# alarm.net
KiCad netlist of a schematic drawn in EAGLE
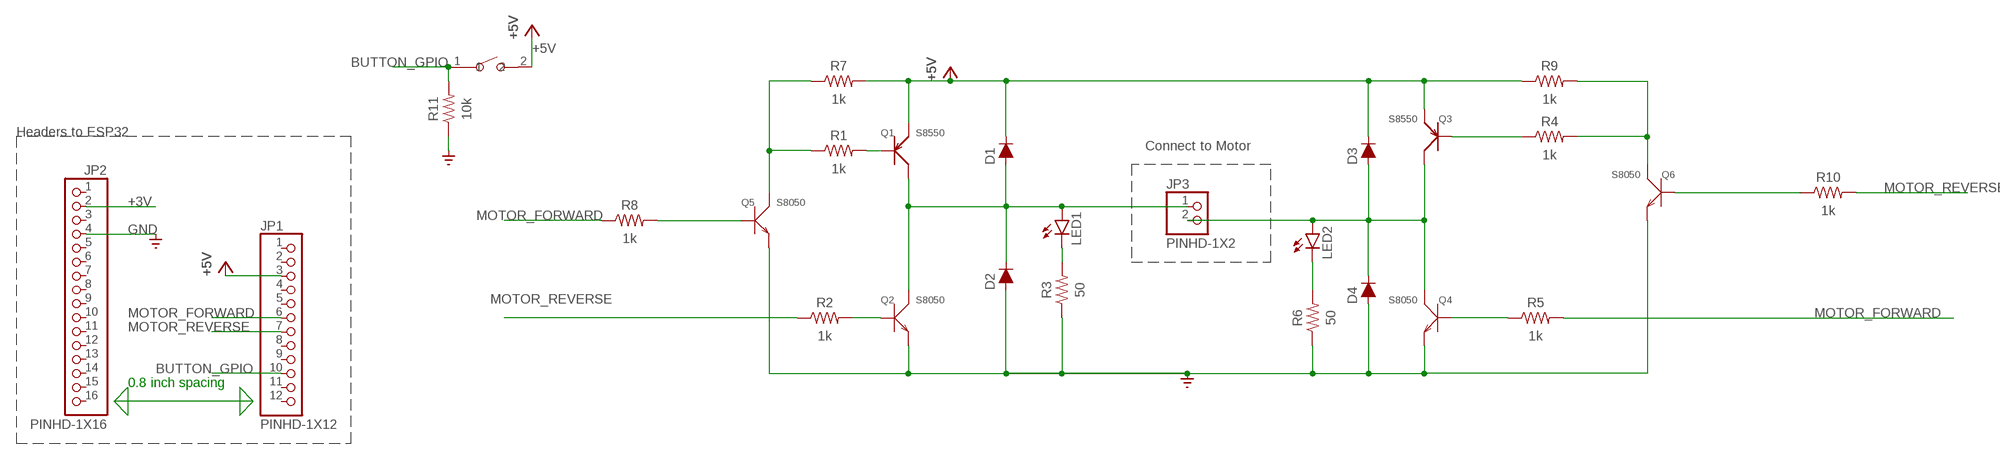
[diagram p0: schematic, sheet 1]

(export (version "E")
  (design (tool "Eeschema 10.0.6"))
  (components
    (comp (ref "D1")
      (value "250mA/100V")
      (footprint "eagle-import:SOD-323")
      (libsource (lib "eagle-import") (part "DIODE-BAS16J"))
    )
    (comp (ref "D2")
      (value "250mA/100V")
      (footprint "eagle-import:SOD-323")
      (libsource (lib "eagle-import") (part "DIODE-BAS16J"))
    )
    (comp (ref "D3")
      (value "250mA/100V")
      (footprint "eagle-import:SOD-323")
      (libsource (lib "eagle-import") (part "DIODE-BAS16J"))
    )
    (comp (ref "D4")
      (value "250mA/100V")
      (footprint "eagle-import:SOD-323")
      (libsource (lib "eagle-import") (part "DIODE-BAS16J"))
    )
    (comp (ref "JP1")
      (value "PINHD-1X12")
      (footprint "eagle-import:1X12")
      (libsource (lib "eagle-import") (part "PINHD-1X12"))
    )
    (comp (ref "JP2")
      (value "PINHD-1X16")
      (footprint "eagle-import:1X16")
      (libsource (lib "eagle-import") (part "PINHD-1X16"))
    )
    (comp (ref "JP3")
      (value "PINHD-1X2")
      (footprint "eagle-import:1X02")
      (libsource (lib "eagle-import") (part "PINHD-1X2"))
    )
    (comp (ref "LED1")
      (value "LED-GREEN0603")
      (footprint "eagle-import:0603-GREEN")
      (libsource (lib "eagle-import") (part "LED-GREEN0603"))
    )
    (comp (ref "LED2")
      (value "LED-ORANGE0603")
      (footprint "eagle-import:0603-ORANGE")
      (libsource (lib "eagle-import") (part "LED-ORANGE0603"))
    )
    (comp (ref "Q1")
      (value "S8550")
      (footprint "eagle-import:SOT-23")
      (libsource (lib "eagle-import") (part "SMD-TRANSISTORS-PNP-25V-500MA-S8550(SOT-23)"))
    )
    (comp (ref "Q2")
      (value "S8050")
      (footprint "eagle-import:SOT-23")
      (libsource (lib "eagle-import") (part "SMD-TRANSISTORS-NPN-25V-500MW-S8050(SOT-23)"))
    )
    (comp (ref "Q3")
      (value "S8550")
      (footprint "eagle-import:SOT-23")
      (libsource (lib "eagle-import") (part "SMD-TRANSISTORS-PNP-25V-500MA-S8550(SOT-23)"))
    )
    (comp (ref "Q4")
      (value "S8050")
      (footprint "eagle-import:SOT-23")
      (libsource (lib "eagle-import") (part "SMD-TRANSISTORS-NPN-25V-500MW-S8050(SOT-23)"))
    )
    (comp (ref "Q5")
      (value "S8050")
      (footprint "eagle-import:SOT-23")
      (libsource (lib "eagle-import") (part "SMD-TRANSISTORS-NPN-25V-500MW-S8050(SOT-23)"))
    )
    (comp (ref "Q6")
      (value "S8050")
      (footprint "eagle-import:SOT-23")
      (libsource (lib "eagle-import") (part "SMD-TRANSISTORS-NPN-25V-500MW-S8050(SOT-23)"))
    )
    (comp (ref "R1")
      (value "1k")
      (footprint "eagle-import:RESC1608X60")
      (libsource (lib "eagle-import") (part "R-USCHIP-0603(1608-METRIC)_"))
    )
    (comp (ref "R2")
      (value "1k")
      (footprint "eagle-import:RESC1608X60")
      (libsource (lib "eagle-import") (part "R-USCHIP-0603(1608-METRIC)_"))
    )
    (comp (ref "R3")
      (value "50")
      (footprint "eagle-import:RESC1608X60")
      (libsource (lib "eagle-import") (part "R-USCHIP-0603(1608-METRIC)_"))
    )
    (comp (ref "R4")
      (value "1k")
      (footprint "eagle-import:RESC1608X60")
      (libsource (lib "eagle-import") (part "R-USCHIP-0603(1608-METRIC)_"))
    )
    (comp (ref "R5")
      (value "1k")
      (footprint "eagle-import:RESC1608X60")
      (libsource (lib "eagle-import") (part "R-USCHIP-0603(1608-METRIC)_"))
    )
    (comp (ref "R6")
      (value "50")
      (footprint "eagle-import:RESC1608X60")
      (libsource (lib "eagle-import") (part "R-USCHIP-0603(1608-METRIC)_"))
    )
    (comp (ref "R7")
      (value "1k")
      (footprint "eagle-import:RESC1608X60")
      (libsource (lib "eagle-import") (part "R-USCHIP-0603(1608-METRIC)_"))
    )
    (comp (ref "R8")
      (value "1k")
      (footprint "eagle-import:RESC1608X60")
      (libsource (lib "eagle-import") (part "R-USCHIP-0603(1608-METRIC)_"))
    )
    (comp (ref "R9")
      (value "1k")
      (footprint "eagle-import:RESC1608X60")
      (libsource (lib "eagle-import") (part "R-USCHIP-0603(1608-METRIC)_"))
    )
    (comp (ref "R10")
      (value "1k")
      (footprint "eagle-import:RESC1608X60")
      (libsource (lib "eagle-import") (part "R-USCHIP-0603(1608-METRIC)_"))
    )
    (comp (ref "R11")
      (value "10k")
      (footprint "eagle-import:RESC1608X60")
      (libsource (lib "eagle-import") (part "R-USCHIP-0603(1608-METRIC)_"))
    )
    (comp (ref "SW1")
      (value "B3U-1000P-2P-SMD")
      (footprint "eagle-import:SW2-2.6-3.0X2.5X1.2+0.4MM")
      (libsource (lib "eagle-import") (part "SMD-BUTTON(2P-3.0X2.5X1.2+0.4MM)-B3U-1000P-2P-SMD"))
    )
  )
  (nets
    (net (code "1") (name "+5V") (class "Default")
      (node (ref "D1") (pin "C") (pinfunction "C_C") (pintype "passive"))
      (node (ref "D3") (pin "C") (pinfunction "C_C") (pintype "passive"))
      (node (ref "JP1") (pin "3") (pinfunction "3_3") (pintype "passive"))
      (node (ref "Q1") (pin "2") (pinfunction "E_2") (pintype "passive"))
      (node (ref "Q3") (pin "2") (pinfunction "E_2") (pintype "passive"))
      (node (ref "R7") (pin "2") (pinfunction "2_2") (pintype "passive"))
      (node (ref "R9") (pin "1") (pinfunction "1_1") (pintype "passive"))
      (node (ref "SW1") (pin "2") (pinfunction "2_2") (pintype "bidirectional"))
    )
    (net (code "2") (name "/+3V") (class "Default")
      (node (ref "JP2") (pin "2") (pinfunction "2_2") (pintype "passive"))
    )
    (net (code "3") (name "/BUTTON_GPIO") (class "Default")
      (node (ref "JP1") (pin "10") (pinfunction "10_10") (pintype "passive"))
      (node (ref "R11") (pin "2") (pinfunction "2_2") (pintype "passive"))
      (node (ref "SW1") (pin "1") (pinfunction "1_1") (pintype "bidirectional"))
    )
    (net (code "4") (name "/MOTOR_FORWARD") (class "Default")
      (node (ref "JP1") (pin "6") (pinfunction "6_6") (pintype "passive"))
      (node (ref "R5") (pin "2") (pinfunction "2_2") (pintype "passive"))
      (node (ref "R8") (pin "1") (pinfunction "1_1") (pintype "passive"))
    )
    (net (code "5") (name "/MOTOR_REVERSE") (class "Default")
      (node (ref "JP1") (pin "7") (pinfunction "7_7") (pintype "passive"))
      (node (ref "R10") (pin "2") (pinfunction "2_2") (pintype "passive"))
      (node (ref "R2") (pin "1") (pinfunction "1_1") (pintype "passive"))
    )
    (net (code "6") (name "Net-(LED1-PadC)") (class "Default")
      (node (ref "LED1") (pin "C") (pinfunction "C_C") (pintype "passive"))
      (node (ref "R3") (pin "2") (pinfunction "2_2") (pintype "passive"))
    )
    (net (code "7") (name "Net-(LED2-PadC)") (class "Default")
      (node (ref "LED2") (pin "C") (pinfunction "C_C") (pintype "passive"))
      (node (ref "R6") (pin "2") (pinfunction "2_2") (pintype "passive"))
    )
    (net (code "8") (name "Net-(Q1-B)") (class "Default")
      (node (ref "Q1") (pin "1") (pinfunction "B_1") (pintype "passive"))
      (node (ref "R1") (pin "2") (pinfunction "2_2") (pintype "passive"))
    )
    (net (code "9") (name "Net-(Q1-C)") (class "Default")
      (node (ref "D1") (pin "A") (pinfunction "A_A") (pintype "passive"))
      (node (ref "D2") (pin "C") (pinfunction "C_C") (pintype "passive"))
      (node (ref "JP3") (pin "1") (pinfunction "1_1") (pintype "passive"))
      (node (ref "LED1") (pin "A") (pinfunction "A_A") (pintype "passive"))
      (node (ref "Q1") (pin "3") (pinfunction "C_3") (pintype "passive"))
      (node (ref "Q2") (pin "3") (pinfunction "C_3") (pintype "passive"))
    )
    (net (code "10") (name "Net-(Q2-B)") (class "Default")
      (node (ref "Q2") (pin "1") (pinfunction "B_1") (pintype "passive"))
      (node (ref "R2") (pin "2") (pinfunction "2_2") (pintype "passive"))
    )
    (net (code "11") (name "Net-(Q3-B)") (class "Default")
      (node (ref "Q3") (pin "1") (pinfunction "B_1") (pintype "passive"))
      (node (ref "R4") (pin "1") (pinfunction "1_1") (pintype "passive"))
    )
    (net (code "12") (name "Net-(Q3-C)") (class "Default")
      (node (ref "D3") (pin "A") (pinfunction "A_A") (pintype "passive"))
      (node (ref "D4") (pin "C") (pinfunction "C_C") (pintype "passive"))
      (node (ref "JP3") (pin "2") (pinfunction "2_2") (pintype "passive"))
      (node (ref "LED2") (pin "A") (pinfunction "A_A") (pintype "passive"))
      (node (ref "Q3") (pin "3") (pinfunction "C_3") (pintype "passive"))
      (node (ref "Q4") (pin "3") (pinfunction "C_3") (pintype "passive"))
    )
    (net (code "13") (name "Net-(Q4-B)") (class "Default")
      (node (ref "Q4") (pin "1") (pinfunction "B_1") (pintype "passive"))
      (node (ref "R5") (pin "1") (pinfunction "1_1") (pintype "passive"))
    )
    (net (code "14") (name "Net-(Q5-B)") (class "Default")
      (node (ref "Q5") (pin "1") (pinfunction "B_1") (pintype "passive"))
      (node (ref "R8") (pin "2") (pinfunction "2_2") (pintype "passive"))
    )
    (net (code "15") (name "Net-(Q5-C)") (class "Default")
      (node (ref "Q5") (pin "3") (pinfunction "C_3") (pintype "passive"))
      (node (ref "R1") (pin "1") (pinfunction "1_1") (pintype "passive"))
      (node (ref "R7") (pin "1") (pinfunction "1_1") (pintype "passive"))
    )
    (net (code "16") (name "Net-(Q6-B)") (class "Default")
      (node (ref "Q6") (pin "1") (pinfunction "B_1") (pintype "passive"))
      (node (ref "R10") (pin "1") (pinfunction "1_1") (pintype "passive"))
    )
    (net (code "17") (name "Net-(Q6-C)") (class "Default")
      (node (ref "Q6") (pin "3") (pinfunction "C_3") (pintype "passive"))
      (node (ref "R4") (pin "2") (pinfunction "2_2") (pintype "passive"))
      (node (ref "R9") (pin "2") (pinfunction "2_2") (pintype "passive"))
    )
    (net (code "18") (name "SUPPLY0_GND_") (class "Default")
      (node (ref "D2") (pin "A") (pinfunction "A_A") (pintype "passive"))
      (node (ref "D4") (pin "A") (pinfunction "A_A") (pintype "passive"))
      (node (ref "JP2") (pin "4") (pinfunction "4_4") (pintype "passive"))
      (node (ref "Q2") (pin "2") (pinfunction "E_2") (pintype "passive"))
      (node (ref "Q4") (pin "2") (pinfunction "E_2") (pintype "passive"))
      (node (ref "Q5") (pin "2") (pinfunction "E_2") (pintype "passive"))
      (node (ref "Q6") (pin "2") (pinfunction "E_2") (pintype "passive"))
      (node (ref "R11") (pin "1") (pinfunction "1_1") (pintype "passive"))
      (node (ref "R3") (pin "1") (pinfunction "1_1") (pintype "passive"))
      (node (ref "R6") (pin "1") (pinfunction "1_1") (pintype "passive"))
    )
    (net (code "19") (name "unconnected-(JP1-Pad1)") (class "Default")
      (node (ref "JP1") (pin "1") (pinfunction "1_1") (pintype "passive"))
    )
    (net (code "20") (name "unconnected-(JP1-Pad2)") (class "Default")
      (node (ref "JP1") (pin "2") (pinfunction "2_2") (pintype "passive"))
    )
    (net (code "21") (name "unconnected-(JP1-Pad4)") (class "Default")
      (node (ref "JP1") (pin "4") (pinfunction "4_4") (pintype "passive"))
    )
    (net (code "22") (name "unconnected-(JP1-Pad5)") (class "Default")
      (node (ref "JP1") (pin "5") (pinfunction "5_5") (pintype "passive"))
    )
    (net (code "23") (name "unconnected-(JP1-Pad8)") (class "Default")
      (node (ref "JP1") (pin "8") (pinfunction "8_8") (pintype "passive"))
    )
    (net (code "24") (name "unconnected-(JP1-Pad9)") (class "Default")
      (node (ref "JP1") (pin "9") (pinfunction "9_9") (pintype "passive"))
    )
    (net (code "25") (name "unconnected-(JP1-Pad11)") (class "Default")
      (node (ref "JP1") (pin "11") (pinfunction "11_11") (pintype "passive"))
    )
    (net (code "26") (name "unconnected-(JP1-Pad12)") (class "Default")
      (node (ref "JP1") (pin "12") (pinfunction "12_12") (pintype "passive"))
    )
    (net (code "27") (name "unconnected-(JP2-Pad1)") (class "Default")
      (node (ref "JP2") (pin "1") (pinfunction "1_1") (pintype "passive"))
    )
    (net (code "28") (name "unconnected-(JP2-Pad3)") (class "Default")
      (node (ref "JP2") (pin "3") (pinfunction "3_3") (pintype "passive"))
    )
    (net (code "29") (name "unconnected-(JP2-Pad5)") (class "Default")
      (node (ref "JP2") (pin "5") (pinfunction "5_5") (pintype "passive"))
    )
    (net (code "30") (name "unconnected-(JP2-Pad6)") (class "Default")
      (node (ref "JP2") (pin "6") (pinfunction "6_6") (pintype "passive"))
    )
    (net (code "31") (name "unconnected-(JP2-Pad7)") (class "Default")
      (node (ref "JP2") (pin "7") (pinfunction "7_7") (pintype "passive"))
    )
    (net (code "32") (name "unconnected-(JP2-Pad8)") (class "Default")
      (node (ref "JP2") (pin "8") (pinfunction "8_8") (pintype "passive"))
    )
    (net (code "33") (name "unconnected-(JP2-Pad9)") (class "Default")
      (node (ref "JP2") (pin "9") (pinfunction "9_9") (pintype "passive"))
    )
    (net (code "34") (name "unconnected-(JP2-Pad10)") (class "Default")
      (node (ref "JP2") (pin "10") (pinfunction "10_10") (pintype "passive"))
    )
    (net (code "35") (name "unconnected-(JP2-Pad11)") (class "Default")
      (node (ref "JP2") (pin "11") (pinfunction "11_11") (pintype "passive"))
    )
    (net (code "36") (name "unconnected-(JP2-Pad12)") (class "Default")
      (node (ref "JP2") (pin "12") (pinfunction "12_12") (pintype "passive"))
    )
    (net (code "37") (name "unconnected-(JP2-Pad13)") (class "Default")
      (node (ref "JP2") (pin "13") (pinfunction "13_13") (pintype "passive"))
    )
    (net (code "38") (name "unconnected-(JP2-Pad14)") (class "Default")
      (node (ref "JP2") (pin "14") (pinfunction "14_14") (pintype "passive"))
    )
    (net (code "39") (name "unconnected-(JP2-Pad15)") (class "Default")
      (node (ref "JP2") (pin "15") (pinfunction "15_15") (pintype "passive"))
    )
    (net (code "40") (name "unconnected-(JP2-Pad16)") (class "Default")
      (node (ref "JP2") (pin "16") (pinfunction "16_16") (pintype "passive"))
    )
  )
)
